# Attiny43u_devboard.net
KiCad netlist of a schematic drawn in EAGLE
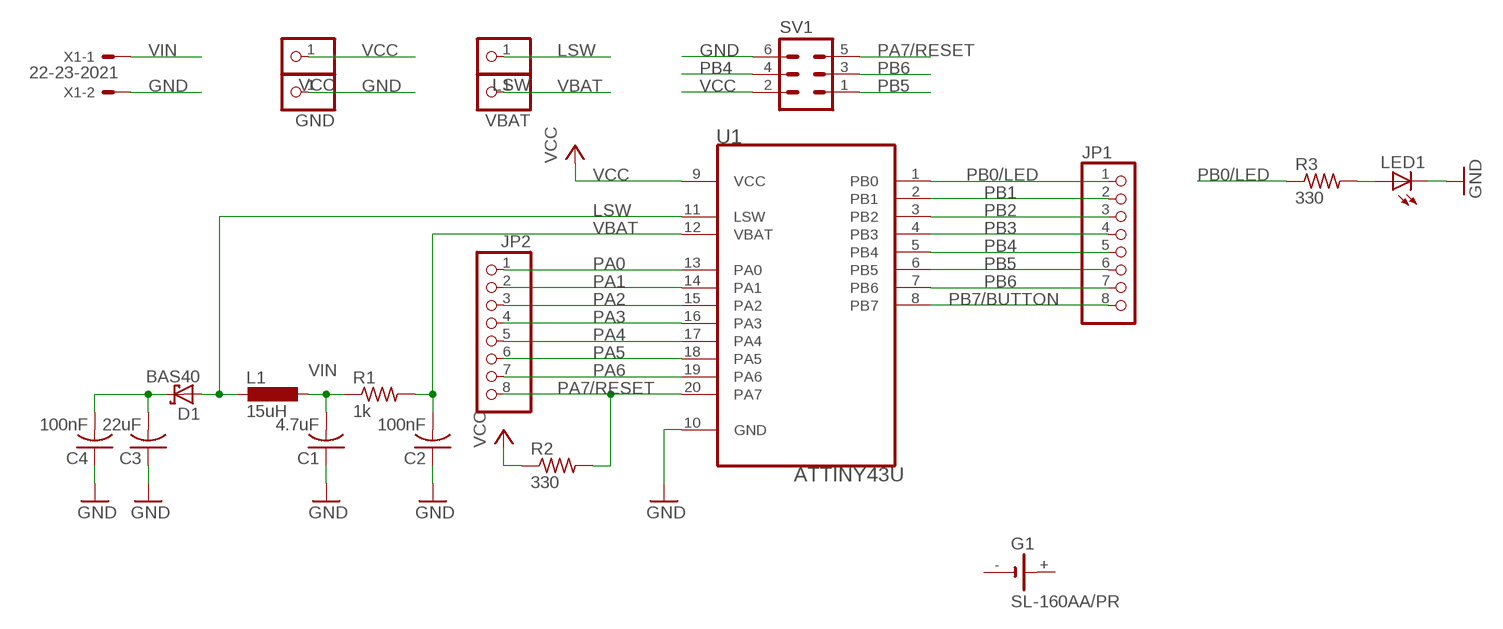
[diagram p0: schematic, sheet 1]

(export (version "E")
  (design (tool "Eeschema 10.0.6"))
  (components
    (comp (ref "C1")
      (value "4.7uF")
      (footprint "eagle-import:C1206K")
      (libsource (lib "eagle-import") (part "C-USC1206K"))
    )
    (comp (ref "C2")
      (value "100nF")
      (footprint "eagle-import:C1206K")
      (libsource (lib "eagle-import") (part "C-USC1206K"))
    )
    (comp (ref "C3")
      (value "22uF")
      (footprint "eagle-import:C1206K")
      (libsource (lib "eagle-import") (part "C-USC1206K"))
    )
    (comp (ref "C4")
      (value "100nF")
      (footprint "eagle-import:C1206K")
      (libsource (lib "eagle-import") (part "C-USC1206K"))
    )
    (comp (ref "D1")
      (value "BAS40")
      (footprint "eagle-import:SOT23")
      (libsource (lib "eagle-import") (part "BAS40"))
    )
    (comp (ref "G1")
      (value "SL-160AA/PR")
      (footprint "eagle-import:SL-160AA_PR")
      (libsource (lib "eagle-import") (part "SL-160AA/PR"))
    )
    (comp (ref "GND")
      (value "PINHD-1X1")
      (footprint "eagle-import:1X01")
      (libsource (lib "eagle-import") (part "PINHD-1X1"))
    )
    (comp (ref "JP1")
      (value "PINHD-1X8")
      (footprint "eagle-import:1X08")
      (libsource (lib "eagle-import") (part "PINHD-1X8"))
    )
    (comp (ref "JP2")
      (value "PINHD-1X8")
      (footprint "eagle-import:1X08")
      (libsource (lib "eagle-import") (part "PINHD-1X8"))
    )
    (comp (ref "L1")
      (value "15uH")
      (footprint "eagle-import:L3225M")
      (libsource (lib "eagle-import") (part "L-EUL3225M"))
    )
    (comp (ref "LED1")
      (value "LEDCHIPLED_1206")
      (footprint "eagle-import:CHIPLED_1206")
      (libsource (lib "eagle-import") (part "LEDCHIPLED_1206"))
    )
    (comp (ref "LSW")
      (value "PINHD-1X1")
      (footprint "eagle-import:1X01")
      (libsource (lib "eagle-import") (part "PINHD-1X1"))
    )
    (comp (ref "R1")
      (value "1k")
      (footprint "eagle-import:M1206")
      (libsource (lib "eagle-import") (part "R-US_M1206"))
    )
    (comp (ref "R2")
      (value "330")
      (footprint "eagle-import:M1206")
      (libsource (lib "eagle-import") (part "R-US_M1206"))
    )
    (comp (ref "R3")
      (value "330")
      (footprint "eagle-import:M1206")
      (libsource (lib "eagle-import") (part "R-US_M1206"))
    )
    (comp (ref "SV1")
      (value "MA03-2")
      (footprint "eagle-import:MA03-2")
      (libsource (lib "eagle-import") (part "MA03-2"))
    )
    (comp (ref "U1")
      (value "ATTINY43U")
      (footprint "eagle-import:SOIC127P1032X265-20N")
      (fields (field (name "MPN") "ATTINY43U-SU"))
      (libsource (lib "eagle-import") (part "ATTINY43U-SU"))
    )
    (comp (ref "VBAT")
      (value "PINHD-1X1")
      (footprint "eagle-import:1X01")
      (libsource (lib "eagle-import") (part "PINHD-1X1"))
    )
    (comp (ref "VCC")
      (value "PINHD-1X1")
      (footprint "eagle-import:1X01")
      (libsource (lib "eagle-import") (part "PINHD-1X1"))
    )
    (comp (ref "X1")
      (value "22-23-2021")
      (footprint "eagle-import:22-23-2021")
      (fields (field (name "MF") "MOLEX"))
      (libsource (lib "eagle-import") (part "22-23-2021"))
    )
  )
  (nets
    (net (code "1") (name "/LSW") (class "Default")
      (node (ref "D1") (pin "1") (pinfunction "A_1") (pintype "passive"))
      (node (ref "L1") (pin "2") (pinfunction "2_2") (pintype "passive"))
      (node (ref "LSW") (pin "1") (pinfunction "1_1") (pintype "passive"))
      (node (ref "U1") (pin "11") (pinfunction "LSW_11") (pintype "passive"))
    )
    (net (code "2") (name "/PA0") (class "Default")
      (node (ref "JP2") (pin "1") (pinfunction "1_1") (pintype "passive"))
      (node (ref "U1") (pin "13") (pinfunction "PA0_13") (pintype "bidirectional"))
    )
    (net (code "3") (name "/PA1") (class "Default")
      (node (ref "JP2") (pin "2") (pinfunction "2_2") (pintype "passive"))
      (node (ref "U1") (pin "14") (pinfunction "PA1_14") (pintype "bidirectional"))
    )
    (net (code "4") (name "/PA2") (class "Default")
      (node (ref "JP2") (pin "3") (pinfunction "3_3") (pintype "passive"))
      (node (ref "U1") (pin "15") (pinfunction "PA2_15") (pintype "bidirectional"))
    )
    (net (code "5") (name "/PA3") (class "Default")
      (node (ref "JP2") (pin "4") (pinfunction "4_4") (pintype "passive"))
      (node (ref "U1") (pin "16") (pinfunction "PA3_16") (pintype "bidirectional"))
    )
    (net (code "6") (name "/PA4") (class "Default")
      (node (ref "JP2") (pin "5") (pinfunction "5_5") (pintype "passive"))
      (node (ref "U1") (pin "17") (pinfunction "PA4_17") (pintype "bidirectional"))
    )
    (net (code "7") (name "/PA5") (class "Default")
      (node (ref "JP2") (pin "6") (pinfunction "6_6") (pintype "passive"))
      (node (ref "U1") (pin "18") (pinfunction "PA5_18") (pintype "bidirectional"))
    )
    (net (code "8") (name "/PA6") (class "Default")
      (node (ref "JP2") (pin "7") (pinfunction "7_7") (pintype "passive"))
      (node (ref "U1") (pin "19") (pinfunction "PA6_19") (pintype "bidirectional"))
    )
    (net (code "9") (name "/PA7{slash}RESET") (class "Default")
      (node (ref "JP2") (pin "8") (pinfunction "8_8") (pintype "passive"))
      (node (ref "R2") (pin "2") (pinfunction "2_2") (pintype "passive"))
      (node (ref "SV1") (pin "5") (pinfunction "5_5") (pintype "passive"))
      (node (ref "U1") (pin "20") (pinfunction "PA7_20") (pintype "bidirectional"))
    )
    (net (code "10") (name "/PB0{slash}LED") (class "Default")
      (node (ref "JP1") (pin "1") (pinfunction "1_1") (pintype "passive"))
      (node (ref "R3") (pin "1") (pinfunction "1_1") (pintype "passive"))
      (node (ref "U1") (pin "1") (pinfunction "PB0_1") (pintype "bidirectional"))
    )
    (net (code "11") (name "/PB1") (class "Default")
      (node (ref "JP1") (pin "2") (pinfunction "2_2") (pintype "passive"))
      (node (ref "U1") (pin "2") (pinfunction "PB1_2") (pintype "bidirectional"))
    )
    (net (code "12") (name "/PB2") (class "Default")
      (node (ref "JP1") (pin "3") (pinfunction "3_3") (pintype "passive"))
      (node (ref "U1") (pin "3") (pinfunction "PB2_3") (pintype "bidirectional"))
    )
    (net (code "13") (name "/PB3") (class "Default")
      (node (ref "JP1") (pin "4") (pinfunction "4_4") (pintype "passive"))
      (node (ref "U1") (pin "4") (pinfunction "PB3_4") (pintype "bidirectional"))
    )
    (net (code "14") (name "/PB4") (class "Default")
      (node (ref "JP1") (pin "5") (pinfunction "5_5") (pintype "passive"))
      (node (ref "SV1") (pin "4") (pinfunction "4_4") (pintype "passive"))
      (node (ref "U1") (pin "5") (pinfunction "PB4_5") (pintype "bidirectional"))
    )
    (net (code "15") (name "/PB5") (class "Default")
      (node (ref "JP1") (pin "6") (pinfunction "6_6") (pintype "passive"))
      (node (ref "SV1") (pin "1") (pinfunction "1_1") (pintype "passive"))
      (node (ref "U1") (pin "6") (pinfunction "PB5_6") (pintype "bidirectional"))
    )
    (net (code "16") (name "/PB6") (class "Default")
      (node (ref "JP1") (pin "7") (pinfunction "7_7") (pintype "passive"))
      (node (ref "SV1") (pin "3") (pinfunction "3_3") (pintype "passive"))
      (node (ref "U1") (pin "7") (pinfunction "PB6_7") (pintype "bidirectional"))
    )
    (net (code "17") (name "/PB7{slash}BUTTON") (class "Default")
      (node (ref "JP1") (pin "8") (pinfunction "8_8") (pintype "passive"))
      (node (ref "U1") (pin "8") (pinfunction "PB7_8") (pintype "bidirectional"))
    )
    (net (code "18") (name "/VBAT") (class "Default")
      (node (ref "C2") (pin "2") (pinfunction "2_2") (pintype "passive"))
      (node (ref "R1") (pin "2") (pinfunction "2_2") (pintype "passive"))
      (node (ref "U1") (pin "12") (pinfunction "VBAT_12") (pintype "passive"))
      (node (ref "VBAT") (pin "1") (pinfunction "1_1") (pintype "passive"))
    )
    (net (code "19") (name "/VIN") (class "Default")
      (node (ref "C1") (pin "2") (pinfunction "2_2") (pintype "passive"))
      (node (ref "L1") (pin "1") (pinfunction "1_1") (pintype "passive"))
      (node (ref "R1") (pin "1") (pinfunction "1_1") (pintype "passive"))
      (node (ref "X1") (pin "1") (pinfunction "S_1") (pintype "passive"))
    )
    (net (code "20") (name "GND") (class "Default")
      (node (ref "C1") (pin "1") (pinfunction "1_1") (pintype "passive"))
      (node (ref "C2") (pin "1") (pinfunction "1_1") (pintype "passive"))
      (node (ref "C3") (pin "1") (pinfunction "1_1") (pintype "passive"))
      (node (ref "C4") (pin "1") (pinfunction "1_1") (pintype "passive"))
      (node (ref "GND") (pin "1") (pinfunction "1_1") (pintype "passive"))
      (node (ref "LED1") (pin "C") (pinfunction "C_C") (pintype "passive"))
      (node (ref "SV1") (pin "6") (pinfunction "6_6") (pintype "passive"))
      (node (ref "U1") (pin "10") (pinfunction "GND_10") (pintype "passive"))
      (node (ref "X1") (pin "2") (pinfunction "S_2") (pintype "passive"))
    )
    (net (code "21") (name "Net-(D1-C)") (class "Default")
      (node (ref "C3") (pin "2") (pinfunction "2_2") (pintype "passive"))
      (node (ref "C4") (pin "2") (pinfunction "2_2") (pintype "passive"))
      (node (ref "D1") (pin "3") (pinfunction "C_3") (pintype "passive"))
    )
    (net (code "22") (name "Net-(LED1-PadA)") (class "Default")
      (node (ref "LED1") (pin "A") (pinfunction "A_A") (pintype "passive"))
      (node (ref "R3") (pin "2") (pinfunction "2_2") (pintype "passive"))
    )
    (net (code "23") (name "VCC") (class "Default")
      (node (ref "R2") (pin "1") (pinfunction "1_1") (pintype "passive"))
      (node (ref "SV1") (pin "2") (pinfunction "2_2") (pintype "passive"))
      (node (ref "U1") (pin "9") (pinfunction "VCC_9") (pintype "power_in"))
      (node (ref "VCC") (pin "1") (pinfunction "1_1") (pintype "passive"))
    )
    (net (code "24") (name "unconnected-(G1-Pad+)") (class "Default")
      (node (ref "G1") (pin "+") (pinfunction "+_+") (pintype "passive"))
    )
    (net (code "25") (name "unconnected-(G1-Pad-)") (class "Default")
      (node (ref "G1") (pin "-") (pinfunction "-_-") (pintype "passive"))
    )
  )
)
